# 24GSchematic.net
KiCad netlist of a schematic drawn in Altium Designer
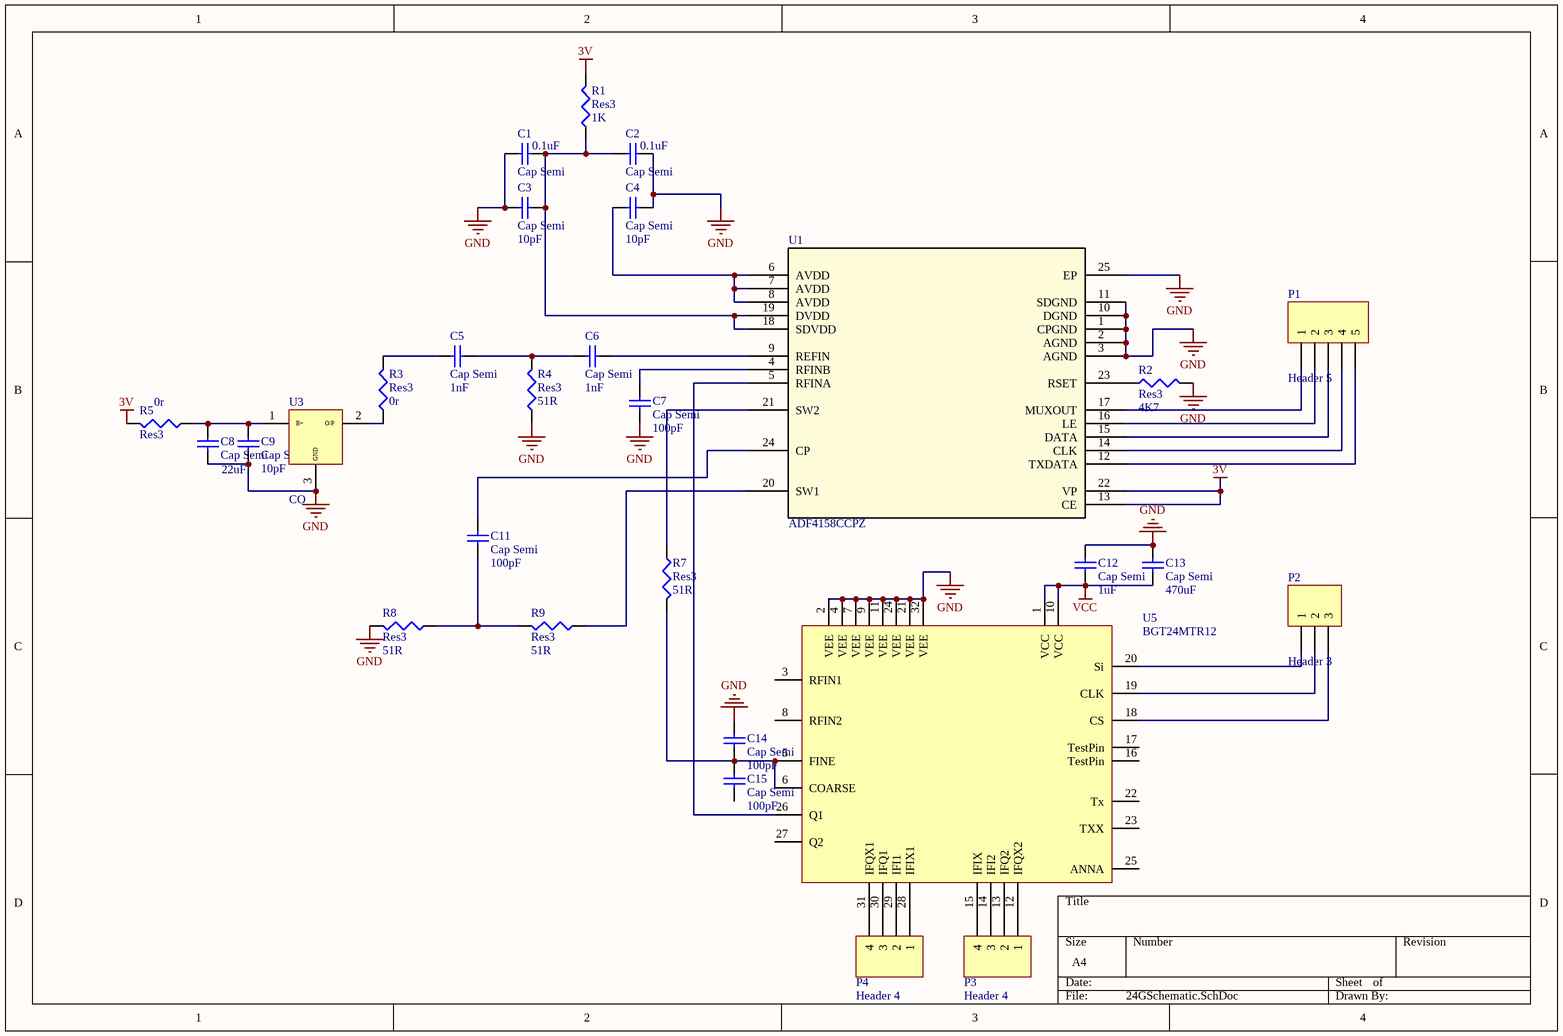
[diagram p0: 24GSchematic.SchDoc]

(export (version "E")
  (design (tool "Eeschema 10.0.6"))
  (components
    (comp (ref "C1")
      (value "Cap Semi")
      (footprint "1608[0603]")
      (description "Capacitor (Semiconductor SIM Model)")
      (fields (field (name "ALTIUM_VALUE") "0.1uF") (field (name "PUBLISHER") "Altium Limited"))
      (libsource (lib "Miscellaneous Devices") (part "Cap Semi"))
    )
    (comp (ref "C2")
      (value "Cap Semi")
      (footprint "1608[0603]")
      (description "Capacitor (Semiconductor SIM Model)")
      (fields (field (name "ALTIUM_VALUE") "0.1uF") (field (name "PUBLISHER") "Altium Limited"))
      (libsource (lib "Miscellaneous Devices") (part "Cap Semi"))
    )
    (comp (ref "C3")
      (value "Cap Semi")
      (footprint "1608[0603]")
      (description "Capacitor (Semiconductor SIM Model)")
      (fields (field (name "ALTIUM_VALUE") "10pF") (field (name "PUBLISHER") "Altium Limited"))
      (libsource (lib "Miscellaneous Devices") (part "Cap Semi"))
    )
    (comp (ref "C4")
      (value "Cap Semi")
      (footprint "1608[0603]")
      (description "Capacitor (Semiconductor SIM Model)")
      (fields (field (name "ALTIUM_VALUE") "10pF") (field (name "PUBLISHER") "Altium Limited"))
      (libsource (lib "Miscellaneous Devices") (part "Cap Semi"))
    )
    (comp (ref "C5")
      (value "Cap Semi")
      (footprint "1608[0603]")
      (description "Capacitor (Semiconductor SIM Model)")
      (fields (field (name "ALTIUM_VALUE") "1nF") (field (name "PUBLISHER") "Altium Limited"))
      (libsource (lib "Miscellaneous Devices") (part "Cap Semi"))
    )
    (comp (ref "C6")
      (value "Cap Semi")
      (footprint "1608[0603]")
      (description "Capacitor (Semiconductor SIM Model)")
      (fields (field (name "ALTIUM_VALUE") "1nF") (field (name "PUBLISHER") "Altium Limited"))
      (libsource (lib "Miscellaneous Devices") (part "Cap Semi"))
    )
    (comp (ref "C7")
      (value "Cap Semi")
      (footprint "1608[0603]")
      (description "Capacitor (Semiconductor SIM Model)")
      (fields (field (name "ALTIUM_VALUE") "100pF") (field (name "PUBLISHER") "Altium Limited"))
      (libsource (lib "Miscellaneous Devices") (part "Cap Semi"))
    )
    (comp (ref "C8")
      (value "Cap Semi")
      (footprint "1608[0603]")
      (description "Capacitor (Semiconductor SIM Model)")
      (fields (field (name "ALTIUM_VALUE") "22uF") (field (name "PUBLISHER") "Altium Limited"))
      (libsource (lib "Miscellaneous Devices") (part "Cap Semi"))
    )
    (comp (ref "C9")
      (value "Cap Semi")
      (footprint "1608[0603]")
      (description "Capacitor (Semiconductor SIM Model)")
      (fields (field (name "ALTIUM_VALUE") "10pF") (field (name "PUBLISHER") "Altium Limited"))
      (libsource (lib "Miscellaneous Devices") (part "Cap Semi"))
    )
    (comp (ref "C11")
      (value "Cap Semi")
      (footprint "1608[0603]")
      (description "Capacitor (Semiconductor SIM Model)")
      (fields (field (name "ALTIUM_VALUE") "100pF") (field (name "PUBLISHER") "Altium Limited"))
      (libsource (lib "Miscellaneous Devices") (part "Cap Semi"))
    )
    (comp (ref "C12")
      (value "Cap Semi")
      (footprint "1608[0603]")
      (description "Capacitor (Semiconductor SIM Model)")
      (fields (field (name "ALTIUM_VALUE") "1uF") (field (name "PUBLISHER") "Altium Limited"))
      (libsource (lib "Miscellaneous Devices") (part "Cap Semi"))
    )
    (comp (ref "C13")
      (value "Cap Semi")
      (footprint "1608[0603]")
      (description "Capacitor (Semiconductor SIM Model)")
      (fields (field (name "ALTIUM_VALUE") "470uF") (field (name "PUBLISHER") "Altium Limited"))
      (libsource (lib "Miscellaneous Devices") (part "Cap Semi"))
    )
    (comp (ref "C14")
      (value "Cap Semi")
      (footprint "1608[0603]")
      (description "Capacitor (Semiconductor SIM Model)")
      (fields (field (name "ALTIUM_VALUE") "100pF") (field (name "PUBLISHER") "Altium Limited"))
      (libsource (lib "Miscellaneous Devices") (part "Cap Semi"))
    )
    (comp (ref "C15")
      (value "Cap Semi")
      (footprint "1608[0603]")
      (description "Capacitor (Semiconductor SIM Model)")
      (fields (field (name "ALTIUM_VALUE") "100pF") (field (name "PUBLISHER") "Altium Limited"))
      (libsource (lib "Miscellaneous Devices") (part "Cap Semi"))
    )
    (comp (ref "P1")
      (value "Header 5")
      (footprint "HDR1X5")
      (description "Header, 5-Pin")
      (fields (field (name "PUBLISHER") "Altium Limited"))
      (libsource (lib "Miscellaneous Connectors") (part "Header 5"))
    )
    (comp (ref "P2")
      (value "Header 3")
      (footprint "HDR1X3")
      (description "Header, 3-Pin")
      (fields (field (name "PUBLISHER") "Altium Limited"))
      (libsource (lib "Miscellaneous Connectors") (part "Header 3"))
    )
    (comp (ref "P3")
      (value "Header 4")
      (footprint "HDR1X4")
      (description "Header, 4-Pin")
      (fields (field (name "PUBLISHER") "Altium Limited"))
      (libsource (lib "Miscellaneous Connectors") (part "Header 4"))
    )
    (comp (ref "P4")
      (value "Header 4")
      (footprint "HDR1X4")
      (description "Header, 4-Pin")
      (fields (field (name "PUBLISHER") "Altium Limited"))
      (libsource (lib "Miscellaneous Connectors") (part "Header 4"))
    )
    (comp (ref "R1")
      (value "Res3")
      (footprint "J1-0603")
      (description "Resistor")
      (fields (field (name "ALTIUM_VALUE") "1K") (field (name "PUBLISHER") "Altium Limited"))
      (libsource (lib "Miscellaneous Devices") (part "Res3"))
    )
    (comp (ref "R2")
      (value "Res3")
      (footprint "J1-0603")
      (description "Resistor")
      (fields (field (name "ALTIUM_VALUE") "4K7") (field (name "PUBLISHER") "Altium Limited"))
      (libsource (lib "Miscellaneous Devices") (part "Res3"))
    )
    (comp (ref "R3")
      (value "Res3")
      (footprint "J1-0603")
      (description "Resistor")
      (fields (field (name "ALTIUM_VALUE") "0r") (field (name "PUBLISHER") "Altium Limited"))
      (libsource (lib "Miscellaneous Devices") (part "Res3"))
    )
    (comp (ref "R4")
      (value "Res3")
      (footprint "J1-0603")
      (description "Resistor")
      (fields (field (name "ALTIUM_VALUE") "51R") (field (name "PUBLISHER") "Altium Limited"))
      (libsource (lib "Miscellaneous Devices") (part "Res3"))
    )
    (comp (ref "R5")
      (value "Res3")
      (footprint "J1-0603")
      (description "Resistor")
      (fields (field (name "ALTIUM_VALUE") "0r") (field (name "PUBLISHER") "Altium Limited"))
      (libsource (lib "Miscellaneous Devices") (part "Res3"))
    )
    (comp (ref "R7")
      (value "Res3")
      (footprint "J1-0603")
      (description "Resistor")
      (fields (field (name "ALTIUM_VALUE") "51R") (field (name "PUBLISHER") "Altium Limited"))
      (libsource (lib "Miscellaneous Devices") (part "Res3"))
    )
    (comp (ref "R8")
      (value "Res3")
      (footprint "J1-0603")
      (description "Resistor")
      (fields (field (name "ALTIUM_VALUE") "51R") (field (name "PUBLISHER") "Altium Limited"))
      (libsource (lib "Miscellaneous Devices") (part "Res3"))
    )
    (comp (ref "R9")
      (value "Res3")
      (footprint "J1-0603")
      (description "Resistor")
      (fields (field (name "ALTIUM_VALUE") "51R") (field (name "PUBLISHER") "Altium Limited"))
      (libsource (lib "Miscellaneous Devices") (part "Res3"))
    )
    (comp (ref "U1")
      (value "ADF4158CCPZ")
      (footprint "CP_24_7")
      (description "Imported")
      (libsource (lib "2016-06-22_14-55-40") (part "ADF4158CCPZ"))
    )
    (comp (ref "U3")
      (value "CO")
      (footprint "FOX801BE-100")
      (libsource (lib "2016-06-22_14-55-40") (part "CO"))
    )
    (comp (ref "U5")
      (value "BGT24MTR12")
      (footprint "QFN50P540X440X90_HS-33N")
      (libsource (lib "2016-06-22_14-55-40") (part "BGT24MTR12"))
    )
  )
  (nets
    (net (code "1") (name "3V") (class "Default")
      (node (ref "R1") (pin "1") (pinfunction "1_1") (pintype "passive"))
      (node (ref "R5") (pin "2") (pinfunction "2_2") (pintype "passive"))
      (node (ref "U1") (pin "13") (pinfunction "CE_13") (pintype "passive"))
      (node (ref "U1") (pin "22") (pinfunction "VP_22") (pintype "passive"))
    )
    (net (code "2") (name "GND") (class "Default")
      (node (ref "C1") (pin "1") (pinfunction "1_1") (pintype "passive"))
      (node (ref "C12") (pin "1") (pinfunction "1_1") (pintype "passive"))
      (node (ref "C13") (pin "1") (pinfunction "1_1") (pintype "passive"))
      (node (ref "C14") (pin "1") (pinfunction "1_1") (pintype "passive"))
      (node (ref "C2") (pin "2") (pinfunction "2_2") (pintype "passive"))
      (node (ref "C3") (pin "1") (pinfunction "1_1") (pintype "passive"))
      (node (ref "C4") (pin "2") (pinfunction "2_2") (pintype "passive"))
      (node (ref "C7") (pin "1") (pinfunction "1_1") (pintype "passive"))
      (node (ref "C8") (pin "1") (pinfunction "1_1") (pintype "passive"))
      (node (ref "C9") (pin "1") (pinfunction "1_1") (pintype "passive"))
      (node (ref "R2") (pin "2") (pinfunction "2_2") (pintype "passive"))
      (node (ref "R4") (pin "1") (pinfunction "1_1") (pintype "passive"))
      (node (ref "R8") (pin "2") (pinfunction "2_2") (pintype "passive"))
      (node (ref "U1") (pin "1") (pinfunction "CPGND_1") (pintype "passive"))
      (node (ref "U1") (pin "10") (pinfunction "DGND_10") (pintype "passive"))
      (node (ref "U1") (pin "11") (pinfunction "SDGND_11") (pintype "passive"))
      (node (ref "U1") (pin "2") (pinfunction "AGND_2") (pintype "passive"))
      (node (ref "U1") (pin "25") (pinfunction "EP_25") (pintype "passive"))
      (node (ref "U1") (pin "3") (pinfunction "AGND_3") (pintype "passive"))
      (node (ref "U3") (pin "3") (pinfunction "GND_3") (pintype "passive"))
      (node (ref "U5") (pin "11") (pinfunction "VEE_11") (pintype "passive"))
      (node (ref "U5") (pin "2") (pinfunction "VEE_2") (pintype "passive"))
      (node (ref "U5") (pin "21") (pinfunction "VEE_21") (pintype "passive"))
      (node (ref "U5") (pin "24") (pinfunction "VEE_24") (pintype "passive"))
      (node (ref "U5") (pin "32") (pinfunction "VEE_32") (pintype "passive"))
      (node (ref "U5") (pin "4") (pinfunction "VEE_4") (pintype "passive"))
      (node (ref "U5") (pin "7") (pinfunction "VEE_7") (pintype "passive"))
      (node (ref "U5") (pin "9") (pinfunction "VEE_9") (pintype "passive"))
    )
    (net (code "3") (name "Net-(C4-Pad1)") (class "Default")
      (node (ref "C4") (pin "1") (pinfunction "1_1") (pintype "passive"))
      (node (ref "U1") (pin "6") (pinfunction "AVDD_6") (pintype "passive"))
      (node (ref "U1") (pin "7") (pinfunction "AVDD_7") (pintype "passive"))
      (node (ref "U1") (pin "8") (pinfunction "AVDD_8") (pintype "passive"))
    )
    (net (code "4") (name "Net-(C5-Pad1)") (class "Default")
      (node (ref "C5") (pin "1") (pinfunction "1_1") (pintype "passive"))
      (node (ref "R3") (pin "2") (pinfunction "2_2") (pintype "passive"))
    )
    (net (code "5") (name "Net-(C5-Pad2)") (class "Default")
      (node (ref "C5") (pin "2") (pinfunction "2_2") (pintype "passive"))
      (node (ref "C6") (pin "1") (pinfunction "1_1") (pintype "passive"))
      (node (ref "R4") (pin "2") (pinfunction "2_2") (pintype "passive"))
    )
    (net (code "6") (name "Net-(C11-Pad1)") (class "Default")
      (node (ref "C11") (pin "1") (pinfunction "1_1") (pintype "passive"))
      (node (ref "R8") (pin "1") (pinfunction "1_1") (pintype "passive"))
      (node (ref "R9") (pin "2") (pinfunction "2_2") (pintype "passive"))
    )
    (net (code "7") (name "Net-(U1-CLK)") (class "Default")
      (node (ref "P1") (pin "4") (pinfunction "4_4") (pintype "passive"))
      (node (ref "U1") (pin "14") (pinfunction "CLK_14") (pintype "passive"))
    )
    (net (code "8") (name "Net-(U1-CP)") (class "Default")
      (node (ref "C11") (pin "2") (pinfunction "2_2") (pintype "passive"))
      (node (ref "U1") (pin "24") (pinfunction "CP_24") (pintype "passive"))
    )
    (net (code "9") (name "Net-(U1-DATA)") (class "Default")
      (node (ref "P1") (pin "3") (pinfunction "3_3") (pintype "passive"))
      (node (ref "U1") (pin "15") (pinfunction "DATA_15") (pintype "passive"))
    )
    (net (code "10") (name "Net-(U1-DVDD)") (class "Default")
      (node (ref "C1") (pin "2") (pinfunction "2_2") (pintype "passive"))
      (node (ref "C2") (pin "1") (pinfunction "1_1") (pintype "passive"))
      (node (ref "C3") (pin "2") (pinfunction "2_2") (pintype "passive"))
      (node (ref "R1") (pin "2") (pinfunction "2_2") (pintype "passive"))
      (node (ref "U1") (pin "18") (pinfunction "SDVDD_18") (pintype "passive"))
      (node (ref "U1") (pin "19") (pinfunction "DVDD_19") (pintype "passive"))
    )
    (net (code "11") (name "Net-(U1-LE)") (class "Default")
      (node (ref "P1") (pin "2") (pinfunction "2_2") (pintype "passive"))
      (node (ref "U1") (pin "16") (pinfunction "LE_16") (pintype "passive"))
    )
    (net (code "12") (name "Net-(U1-MUXOUT)") (class "Default")
      (node (ref "P1") (pin "1") (pinfunction "1_1") (pintype "passive"))
      (node (ref "U1") (pin "17") (pinfunction "MUXOUT_17") (pintype "passive"))
    )
    (net (code "13") (name "Net-(U1-REFIN)") (class "Default")
      (node (ref "C6") (pin "2") (pinfunction "2_2") (pintype "passive"))
      (node (ref "U1") (pin "9") (pinfunction "REFIN_9") (pintype "passive"))
    )
    (net (code "14") (name "Net-(U1-RFINA)") (class "Default")
      (node (ref "U1") (pin "5") (pinfunction "RFINA_5") (pintype "passive"))
      (node (ref "U5") (pin "26") (pinfunction "Q1_26") (pintype "passive"))
    )
    (net (code "15") (name "Net-(U1-RFINB)") (class "Default")
      (node (ref "C7") (pin "2") (pinfunction "2_2") (pintype "passive"))
      (node (ref "U1") (pin "4") (pinfunction "RFINB_4") (pintype "passive"))
    )
    (net (code "16") (name "Net-(U1-RSET)") (class "Default")
      (node (ref "R2") (pin "1") (pinfunction "1_1") (pintype "passive"))
      (node (ref "U1") (pin "23") (pinfunction "RSET_23") (pintype "passive"))
    )
    (net (code "17") (name "Net-(U1-SW1)") (class "Default")
      (node (ref "R9") (pin "1") (pinfunction "1_1") (pintype "passive"))
      (node (ref "U1") (pin "20") (pinfunction "SW1_20") (pintype "passive"))
    )
    (net (code "18") (name "Net-(U1-SW2)") (class "Default")
      (node (ref "R7") (pin "1") (pinfunction "1_1") (pintype "passive"))
      (node (ref "U1") (pin "21") (pinfunction "SW2_21") (pintype "passive"))
    )
    (net (code "19") (name "Net-(U1-TXDATA)") (class "Default")
      (node (ref "P1") (pin "5") (pinfunction "5_5") (pintype "passive"))
      (node (ref "U1") (pin "12") (pinfunction "TXDATA_12") (pintype "passive"))
    )
    (net (code "20") (name "Net-(U3-B+)") (class "Default")
      (node (ref "C8") (pin "2") (pinfunction "2_2") (pintype "passive"))
      (node (ref "C9") (pin "2") (pinfunction "2_2") (pintype "passive"))
      (node (ref "R5") (pin "1") (pinfunction "1_1") (pintype "passive"))
      (node (ref "U3") (pin "1") (pinfunction "B+_1") (pintype "passive"))
    )
    (net (code "21") (name "Net-(U3-O{slash}P)") (class "Default")
      (node (ref "R3") (pin "1") (pinfunction "1_1") (pintype "passive"))
      (node (ref "U3") (pin "2") (pinfunction "O/P_2") (pintype "passive"))
    )
    (net (code "22") (name "Net-(U5-CLK)") (class "Default")
      (node (ref "P2") (pin "2") (pinfunction "2_2") (pintype "passive"))
      (node (ref "U5") (pin "19") (pinfunction "CLK_19") (pintype "passive"))
    )
    (net (code "23") (name "Net-(U5-COARSE)") (class "Default")
      (node (ref "C14") (pin "2") (pinfunction "2_2") (pintype "passive"))
      (node (ref "C15") (pin "1") (pinfunction "1_1") (pintype "passive"))
      (node (ref "R7") (pin "2") (pinfunction "2_2") (pintype "passive"))
      (node (ref "U5") (pin "5") (pinfunction "FINE_5") (pintype "passive"))
      (node (ref "U5") (pin "6") (pinfunction "COARSE_6") (pintype "passive"))
    )
    (net (code "24") (name "Net-(U5-CS)") (class "Default")
      (node (ref "P2") (pin "3") (pinfunction "3_3") (pintype "passive"))
      (node (ref "U5") (pin "18") (pinfunction "CS_18") (pintype "passive"))
    )
    (net (code "25") (name "Net-(U5-IFI1)") (class "Default")
      (node (ref "P4") (pin "2") (pinfunction "2_2") (pintype "passive"))
      (node (ref "U5") (pin "29") (pinfunction "IFI1_29") (pintype "passive"))
    )
    (net (code "26") (name "Net-(U5-IFI2)") (class "Default")
      (node (ref "P3") (pin "3") (pinfunction "3_3") (pintype "passive"))
      (node (ref "U5") (pin "14") (pinfunction "IFI2_14") (pintype "passive"))
    )
    (net (code "27") (name "Net-(U5-IFIX)") (class "Default")
      (node (ref "P3") (pin "4") (pinfunction "4_4") (pintype "passive"))
      (node (ref "U5") (pin "15") (pinfunction "IFIX_15") (pintype "passive"))
    )
    (net (code "28") (name "Net-(U5-IFIX1)") (class "Default")
      (node (ref "P4") (pin "1") (pinfunction "1_1") (pintype "passive"))
      (node (ref "U5") (pin "28") (pinfunction "IFIX1_28") (pintype "passive"))
    )
    (net (code "29") (name "Net-(U5-IFQ1)") (class "Default")
      (node (ref "P4") (pin "3") (pinfunction "3_3") (pintype "passive"))
      (node (ref "U5") (pin "30") (pinfunction "IFQ1_30") (pintype "passive"))
    )
    (net (code "30") (name "Net-(U5-IFQ2)") (class "Default")
      (node (ref "P3") (pin "2") (pinfunction "2_2") (pintype "passive"))
      (node (ref "U5") (pin "13") (pinfunction "IFQ2_13") (pintype "passive"))
    )
    (net (code "31") (name "Net-(U5-IFQX1)") (class "Default")
      (node (ref "P4") (pin "4") (pinfunction "4_4") (pintype "passive"))
      (node (ref "U5") (pin "31") (pinfunction "IFQX1_31") (pintype "passive"))
    )
    (net (code "32") (name "Net-(U5-IFQX2)") (class "Default")
      (node (ref "P3") (pin "1") (pinfunction "1_1") (pintype "passive"))
      (node (ref "U5") (pin "12") (pinfunction "IFQX2_12") (pintype "passive"))
    )
    (net (code "33") (name "Net-(U5-Si)") (class "Default")
      (node (ref "P2") (pin "1") (pinfunction "1_1") (pintype "passive"))
      (node (ref "U5") (pin "20") (pinfunction "Si_20") (pintype "passive"))
    )
    (net (code "34") (name "VCC") (class "Default")
      (node (ref "C12") (pin "2") (pinfunction "2_2") (pintype "passive"))
      (node (ref "C13") (pin "2") (pinfunction "2_2") (pintype "passive"))
      (node (ref "U5") (pin "1") (pinfunction "VCC_1") (pintype "passive"))
      (node (ref "U5") (pin "10") (pinfunction "VCC_10") (pintype "passive"))
    )
    (net (code "35") (name "unconnected-(C15-Pad2)") (class "Default")
      (node (ref "C15") (pin "2") (pinfunction "2_2") (pintype "passive"))
    )
    (net (code "36") (name "unconnected-(U5-ANNA-Pad25)") (class "Default")
      (node (ref "U5") (pin "25") (pinfunction "ANNA_25") (pintype "passive"))
    )
    (net (code "37") (name "unconnected-(U5-Q2-Pad27)") (class "Default")
      (node (ref "U5") (pin "27") (pinfunction "Q2_27") (pintype "passive"))
    )
    (net (code "38") (name "unconnected-(U5-RFIN1-Pad3)") (class "Default")
      (node (ref "U5") (pin "3") (pinfunction "RFIN1_3") (pintype "passive"))
    )
    (net (code "39") (name "unconnected-(U5-RFIN2-Pad8)") (class "Default")
      (node (ref "U5") (pin "8") (pinfunction "RFIN2_8") (pintype "passive"))
    )
    (net (code "40") (name "unconnected-(U5-TXX-Pad23)") (class "Default")
      (node (ref "U5") (pin "23") (pinfunction "TXX_23") (pintype "passive"))
    )
    (net (code "41") (name "unconnected-(U5-TestPin-Pad16)") (class "Default")
      (node (ref "U5") (pin "16") (pinfunction "TestPin_16") (pintype "passive"))
    )
    (net (code "42") (name "unconnected-(U5-TestPin-Pad17)") (class "Default")
      (node (ref "U5") (pin "17") (pinfunction "TestPin_17") (pintype "passive"))
    )
    (net (code "43") (name "unconnected-(U5-Tx-Pad22)") (class "Default")
      (node (ref "U5") (pin "22") (pinfunction "Tx_22") (pintype "passive"))
    )
  )
)
